# USB_to_MBUS.net
KiCad netlist of a schematic drawn in EAGLE
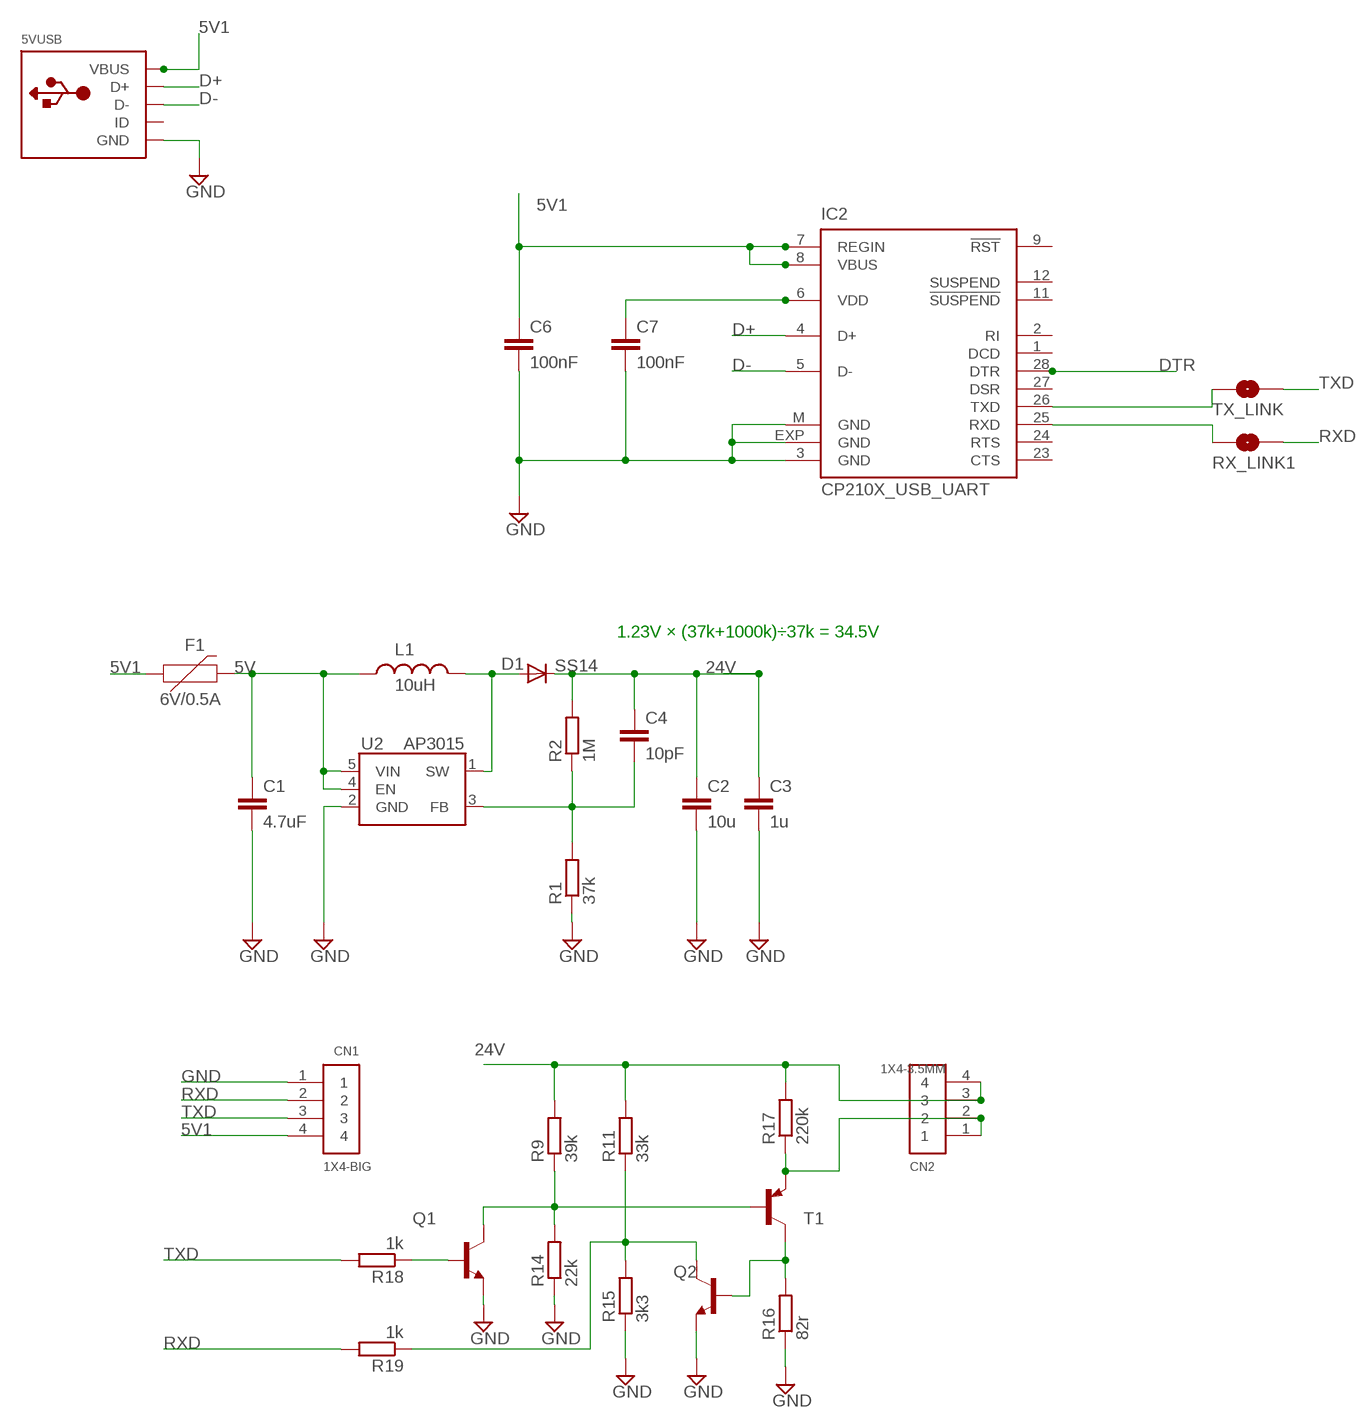
[diagram p0: schematic, sheet 1]

(export (version "E")
  (design (tool "Eeschema 10.0.6"))
  (components
    (comp (ref "5VUSB")
      (value "USBMOLEX")
      (footprint "eagle-import:USB-MINIB-THM-MOLEX")
      (libsource (lib "eagle-import") (part "USBMOLEX"))
    )
    (comp (ref "C1")
      (value "4.7uF")
      (footprint "eagle-import:0603")
      (libsource (lib "eagle-import") (part "1.0UF-0603-16V-10%"))
    )
    (comp (ref "C2")
      (value "10u")
      (footprint "eagle-import:1206")
      (libsource (lib "eagle-import") (part "1.0UF-1206-50V-10%"))
    )
    (comp (ref "C3")
      (value "1u")
      (footprint "eagle-import:1206")
      (libsource (lib "eagle-import") (part "1.0UF-1206-50V-10%"))
    )
    (comp (ref "C4")
      (value "10pF")
      (footprint "eagle-import:0603-CAP")
      (libsource (lib "eagle-import") (part "CAP0603-CAP"))
    )
    (comp (ref "C6")
      (value "100nF")
      (footprint "eagle-import:0603-CAP")
      (libsource (lib "eagle-import") (part "CAP0603-CAP"))
    )
    (comp (ref "C7")
      (value "100nF")
      (footprint "eagle-import:0603-CAP")
      (libsource (lib "eagle-import") (part "CAP0603-CAP"))
    )
    (comp (ref "CN1")
      (value "1X4-BIG")
      (footprint "eagle-import:1X04-BIG")
      (libsource (lib "eagle-import") (part "1X4-BIG"))
    )
    (comp (ref "CN2")
      (value "1X4-3.5MM")
      (footprint "eagle-import:1X04-3.5MM")
      (libsource (lib "eagle-import") (part "adafruit_420_1X4-3.5MM"))
    )
    (comp (ref "D1")
      (value "SS14")
      (footprint "eagle-import:SOD-123")
      (libsource (lib "eagle-import") (part "DIODESOD-123"))
    )
    (comp (ref "F1")
      (value "6V/0.5A")
      (footprint "eagle-import:1206")
      (libsource (lib "eagle-import") (part "PPTC_HALF-AMP"))
    )
    (comp (ref "IC2")
      (value "CP210X_USB_UART")
      (footprint "eagle-import:MLP28")
      (libsource (lib "eagle-import") (part "CP210X_USB_UART"))
    )
    (comp (ref "L1")
      (value "10uH")
      (footprint "eagle-import:CR54")
      (libsource (lib "eagle-import") (part "INDUCTORCR54"))
    )
    (comp (ref "Q1")
      (value "BC808-NPN-SOT23-BEC")
      (footprint "eagle-import:SOT23-BEC")
      (libsource (lib "eagle-import") (part "-NPN-SOT23-BECBC808"))
    )
    (comp (ref "Q2")
      (value "BC808-NPN-SOT23-BEC")
      (footprint "eagle-import:SOT23-BEC")
      (libsource (lib "eagle-import") (part "-NPN-SOT23-BECBC808"))
    )
    (comp (ref "R1")
      (value "37k")
      (footprint "eagle-import:R0603")
      (libsource (lib "eagle-import") (part "R-EU_R0603"))
    )
    (comp (ref "R2")
      (value "1M")
      (footprint "eagle-import:R0603")
      (libsource (lib "eagle-import") (part "R-EU_R0603"))
    )
    (comp (ref "R9")
      (value "39k")
      (footprint "eagle-import:R0603")
      (libsource (lib "eagle-import") (part "R-EU_R0603"))
    )
    (comp (ref "R11")
      (value "33k")
      (footprint "eagle-import:R0603")
      (libsource (lib "eagle-import") (part "R-EU_R0603"))
    )
    (comp (ref "R14")
      (value "22k")
      (footprint "eagle-import:R0603")
      (libsource (lib "eagle-import") (part "R-EU_R0603"))
    )
    (comp (ref "R15")
      (value "3k3")
      (footprint "eagle-import:R0603")
      (libsource (lib "eagle-import") (part "R-EU_R0603"))
    )
    (comp (ref "R16")
      (value "82r")
      (footprint "eagle-import:R0603")
      (libsource (lib "eagle-import") (part "R-EU_R0603"))
    )
    (comp (ref "R17")
      (value "220k")
      (footprint "eagle-import:R0603")
      (libsource (lib "eagle-import") (part "R-EU_R0603"))
    )
    (comp (ref "R18")
      (value "1k")
      (footprint "eagle-import:R0603")
      (libsource (lib "eagle-import") (part "R-EU_R0603"))
    )
    (comp (ref "R19")
      (value "1k")
      (footprint "eagle-import:R0603")
      (libsource (lib "eagle-import") (part "R-EU_R0603"))
    )
    (comp (ref "RX_LINK1")
      (value "SOLDERJUMPERNC")
      (footprint "eagle-import:SJ_2S")
      (libsource (lib "eagle-import") (part "SOLDERJUMPERNC"))
    )
    (comp (ref "T1")
      (value "BC807-16-PNP-SOT23-BEC")
      (footprint "eagle-import:SOT23-BEC")
      (libsource (lib "eagle-import") (part "-PNP-SOT23-BECBC807-16"))
    )
    (comp (ref "TX_LINK")
      (value "SOLDERJUMPERNC")
      (footprint "eagle-import:SJ_2S")
      (libsource (lib "eagle-import") (part "SOLDERJUMPERNC"))
    )
    (comp (ref "U2")
      (value "AP3015")
      (footprint "eagle-import:SOT-23-5")
      (libsource (lib "eagle-import") (part "AP3015"))
    )
  )
  (nets
    (net (code "1") (name "/5V") (class "Default")
      (node (ref "C1") (pin "1") (pinfunction "1_1") (pintype "passive"))
      (node (ref "F1") (pin "2") (pinfunction "2_2") (pintype "bidirectional"))
      (node (ref "L1") (pin "P$1") (pinfunction "1_P$1") (pintype "passive"))
      (node (ref "U2") (pin "4") (pinfunction "EN_4") (pintype "input"))
      (node (ref "U2") (pin "5") (pinfunction "VIN_5") (pintype "power_in"))
    )
    (net (code "2") (name "/5V1") (class "Default")
      (node (ref "5VUSB") (pin "VBUS") (pinfunction "VBUS_VBUS") (pintype "power_in"))
      (node (ref "C6") (pin "1") (pinfunction "1_1") (pintype "passive"))
      (node (ref "CN1") (pin "4") (pinfunction "4_4") (pintype "bidirectional"))
      (node (ref "F1") (pin "1") (pinfunction "1_1") (pintype "bidirectional"))
      (node (ref "IC2") (pin "7") (pinfunction "REGIN_7") (pintype "passive"))
      (node (ref "IC2") (pin "8") (pinfunction "VBUS_8") (pintype "input"))
    )
    (net (code "3") (name "/24V") (class "Default")
      (node (ref "C2") (pin "1") (pinfunction "1_1") (pintype "passive"))
      (node (ref "C3") (pin "1") (pinfunction "1_1") (pintype "passive"))
      (node (ref "C4") (pin "1") (pinfunction "1_1") (pintype "passive"))
      (node (ref "CN2") (pin "3") (pinfunction "3_3") (pintype "bidirectional"))
      (node (ref "CN2") (pin "4") (pinfunction "4_4") (pintype "bidirectional"))
      (node (ref "D1") (pin "C") (pinfunction "C_C") (pintype "passive"))
      (node (ref "R11") (pin "2") (pinfunction "2_2") (pintype "passive"))
      (node (ref "R17") (pin "2") (pinfunction "2_2") (pintype "passive"))
      (node (ref "R2") (pin "2") (pinfunction "2_2") (pintype "passive"))
      (node (ref "R9") (pin "2") (pinfunction "2_2") (pintype "passive"))
    )
    (net (code "4") (name "/D+") (class "Default")
      (node (ref "5VUSB") (pin "D+") (pinfunction "D+_D+") (pintype "bidirectional"))
      (node (ref "IC2") (pin "4") (pinfunction "D+_4") (pintype "bidirectional"))
    )
    (net (code "5") (name "/D-") (class "Default")
      (node (ref "5VUSB") (pin "D-") (pinfunction "D-_D-") (pintype "bidirectional"))
      (node (ref "IC2") (pin "5") (pinfunction "D-_5") (pintype "bidirectional"))
    )
    (net (code "6") (name "/DTR") (class "Default")
      (node (ref "IC2") (pin "28") (pinfunction "DTR_28") (pintype "output"))
    )
    (net (code "7") (name "/RXD") (class "Default")
      (node (ref "CN1") (pin "2") (pinfunction "2_2") (pintype "bidirectional"))
      (node (ref "R19") (pin "2") (pinfunction "2_2") (pintype "passive"))
      (node (ref "RX_LINK1") (pin "2") (pinfunction "2_2") (pintype "passive"))
    )
    (net (code "8") (name "/TXD") (class "Default")
      (node (ref "CN1") (pin "3") (pinfunction "3_3") (pintype "bidirectional"))
      (node (ref "R18") (pin "2") (pinfunction "2_2") (pintype "passive"))
      (node (ref "TX_LINK") (pin "2") (pinfunction "2_2") (pintype "passive"))
    )
    (net (code "9") (name "GND") (class "Default")
      (node (ref "5VUSB") (pin "GND") (pinfunction "GND_GND") (pintype "power_in"))
      (node (ref "C1") (pin "2") (pinfunction "2_2") (pintype "passive"))
      (node (ref "C2") (pin "2") (pinfunction "2_2") (pintype "passive"))
      (node (ref "C3") (pin "2") (pinfunction "2_2") (pintype "passive"))
      (node (ref "C6") (pin "2") (pinfunction "2_2") (pintype "passive"))
      (node (ref "C7") (pin "2") (pinfunction "2_2") (pintype "passive"))
      (node (ref "CN1") (pin "1") (pinfunction "1_1") (pintype "bidirectional"))
      (node (ref "IC2") (pin "3") (pinfunction "GND_3") (pintype "power_in"))
      (node (ref "IC2") (pin "EXP") (pinfunction "GND_EXP") (pintype "power_in"))
      (node (ref "IC2") (pin "M") (pinfunction "GND_M") (pintype "power_in"))
      (node (ref "Q1") (pin "E") (pinfunction "E_E") (pintype "passive"))
      (node (ref "Q2") (pin "E") (pinfunction "E_E") (pintype "passive"))
      (node (ref "R1") (pin "1") (pinfunction "1_1") (pintype "passive"))
      (node (ref "R14") (pin "1") (pinfunction "1_1") (pintype "passive"))
      (node (ref "R15") (pin "1") (pinfunction "1_1") (pintype "passive"))
      (node (ref "R16") (pin "1") (pinfunction "1_1") (pintype "passive"))
      (node (ref "U2") (pin "2") (pinfunction "GND_2") (pintype "power_in"))
    )
    (net (code "10") (name "Net-(CN2-Pad1)") (class "Default")
      (node (ref "CN2") (pin "1") (pinfunction "1_1") (pintype "bidirectional"))
      (node (ref "CN2") (pin "2") (pinfunction "2_2") (pintype "bidirectional"))
      (node (ref "R17") (pin "1") (pinfunction "1_1") (pintype "passive"))
      (node (ref "T1") (pin "E") (pinfunction "E_E") (pintype "passive"))
    )
    (net (code "11") (name "Net-(IC2-RXD)") (class "Default")
      (node (ref "IC2") (pin "25") (pinfunction "RXD_25") (pintype "input"))
      (node (ref "RX_LINK1") (pin "1") (pinfunction "1_1") (pintype "passive"))
    )
    (net (code "12") (name "Net-(IC2-TXD)") (class "Default")
      (node (ref "IC2") (pin "26") (pinfunction "TXD_26") (pintype "output"))
      (node (ref "TX_LINK") (pin "1") (pinfunction "1_1") (pintype "passive"))
    )
    (net (code "13") (name "Net-(IC2-VDD)") (class "Default")
      (node (ref "C7") (pin "1") (pinfunction "1_1") (pintype "passive"))
      (node (ref "IC2") (pin "6") (pinfunction "VDD_6") (pintype "power_in"))
    )
    (net (code "14") (name "Net-(L1-2)") (class "Default")
      (node (ref "D1") (pin "A") (pinfunction "A_A") (pintype "passive"))
      (node (ref "L1") (pin "P$2") (pinfunction "2_P$2") (pintype "passive"))
      (node (ref "U2") (pin "1") (pinfunction "SW_1") (pintype "output"))
    )
    (net (code "15") (name "Net-(Q1-PadB)") (class "Default")
      (node (ref "Q1") (pin "B") (pinfunction "B_B") (pintype "passive"))
      (node (ref "R18") (pin "1") (pinfunction "1_1") (pintype "passive"))
    )
    (net (code "16") (name "Net-(Q1-PadC)") (class "Default")
      (node (ref "Q1") (pin "C") (pinfunction "C_C") (pintype "passive"))
      (node (ref "R14") (pin "2") (pinfunction "2_2") (pintype "passive"))
      (node (ref "R9") (pin "1") (pinfunction "1_1") (pintype "passive"))
      (node (ref "T1") (pin "B") (pinfunction "B_B") (pintype "passive"))
    )
    (net (code "17") (name "Net-(Q2-PadB)") (class "Default")
      (node (ref "Q2") (pin "B") (pinfunction "B_B") (pintype "passive"))
      (node (ref "R16") (pin "2") (pinfunction "2_2") (pintype "passive"))
      (node (ref "T1") (pin "C") (pinfunction "C_C") (pintype "passive"))
    )
    (net (code "18") (name "Net-(Q2-PadC)") (class "Default")
      (node (ref "Q2") (pin "C") (pinfunction "C_C") (pintype "passive"))
      (node (ref "R11") (pin "1") (pinfunction "1_1") (pintype "passive"))
      (node (ref "R15") (pin "2") (pinfunction "2_2") (pintype "passive"))
      (node (ref "R19") (pin "1") (pinfunction "1_1") (pintype "passive"))
    )
    (net (code "19") (name "Net-(U2-FB)") (class "Default")
      (node (ref "C4") (pin "2") (pinfunction "2_2") (pintype "passive"))
      (node (ref "R1") (pin "2") (pinfunction "2_2") (pintype "passive"))
      (node (ref "R2") (pin "1") (pinfunction "1_1") (pintype "passive"))
      (node (ref "U2") (pin "3") (pinfunction "FB_3") (pintype "input"))
    )
    (net (code "20") (name "unconnected-(5VUSB-PadID)") (class "Default")
      (node (ref "5VUSB") (pin "ID") (pinfunction "ID_ID") (pintype "bidirectional"))
    )
    (net (code "21") (name "unconnected-(IC2-CTS-Pad23)") (class "Default")
      (node (ref "IC2") (pin "23") (pinfunction "CTS_23") (pintype "input"))
    )
    (net (code "22") (name "unconnected-(IC2-DCD-Pad1)") (class "Default")
      (node (ref "IC2") (pin "1") (pinfunction "DCD_1") (pintype "input"))
    )
    (net (code "23") (name "unconnected-(IC2-DSR-Pad27)") (class "Default")
      (node (ref "IC2") (pin "27") (pinfunction "DSR_27") (pintype "input"))
    )
    (net (code "24") (name "unconnected-(IC2-RI-Pad2)") (class "Default")
      (node (ref "IC2") (pin "2") (pinfunction "RI_2") (pintype "input"))
    )
    (net (code "25") (name "unconnected-(IC2-RTS-Pad24)") (class "Default")
      (node (ref "IC2") (pin "24") (pinfunction "RTS_24") (pintype "output"))
    )
    (net (code "26") (name "unconnected-(IC2-SUSPEND-Pad12)") (class "Default")
      (node (ref "IC2") (pin "12") (pinfunction "SUSPEND_12") (pintype "output"))
    )
    (net (code "27") (name "unconnected-(IC2-~{RST}-Pad9)") (class "Default")
      (node (ref "IC2") (pin "9") (pinfunction "~{RST}_9") (pintype "bidirectional"))
    )
    (net (code "28") (name "unconnected-(IC2-~{SUSPEND}-Pad11)") (class "Default")
      (node (ref "IC2") (pin "11") (pinfunction "~{SUSPEND}_11") (pintype "output"))
    )
  )
)
